# uSD.net
KiCad netlist of a schematic drawn in Altium Designer
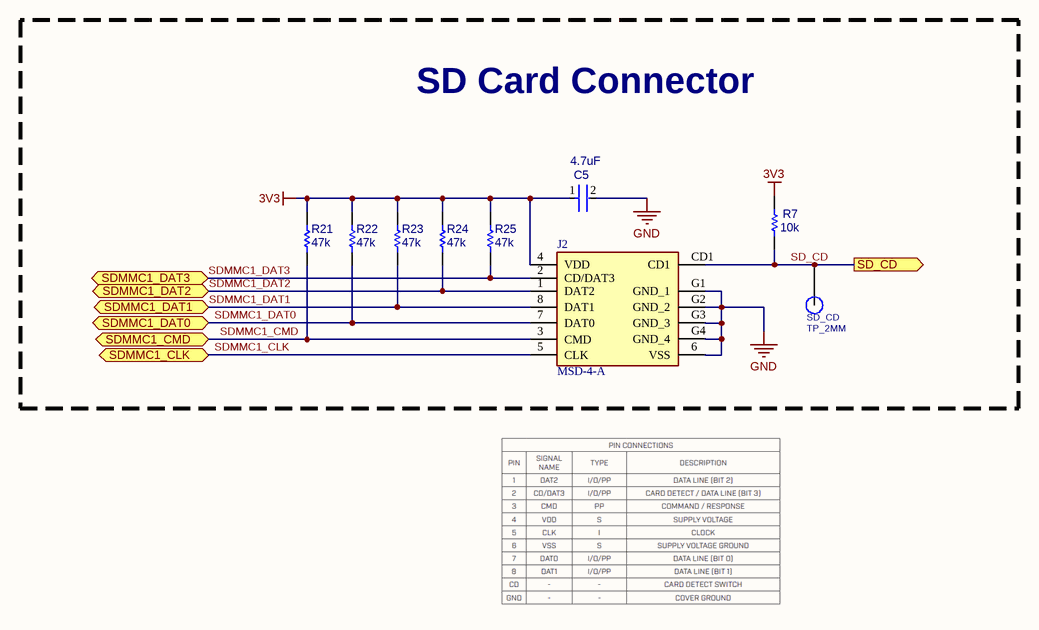
[diagram p0: uSD.SchDoc]

(export (version "E")
  (design (tool "Eeschema 10.0.6"))
  (components
    (comp (ref "C5")
      (value "CC0603KRX7R9BB103")
      (footprint "FP-CC0603-DA-MFG")
      (description "CAP CER 10000PF 50V X7R 0603")
      (fields (field (name "TOLERANCE") "0.1") (field (name "MANUFACTURER") "YAGEO"))
      (libsource (lib "Altium Content Vault") (part "11868f565c42a9108669ba33697ecf6"))
    )
    (comp (ref "J2")
      (value "MSD-4-A")
      (footprint "MSD4A")
      (description "Connector")
      (fields (field (name "MOUSER PART NUMBER") "179-MSD-4-A"))
      (libsource (lib "C2S") (part "MSD-4-A"))
    )
    (comp (ref "R7")
      (value "RC0603JR-070RL")
      (footprint "RESC1608X55X25ML10T15")
      (description "Chip Resistor, 0 Ohm, +/- 5%, 0.1 W, -55 to 155 degC, 0603 (1608 Metric), RoHS, Tape and Reel")
      (fields (field (name "TOLERANCE") "5%") (field (name "MANUFACTURER") "Yageo"))
      (libsource (lib "Altium Content Vault") (part "RES-2"))
    )
    (comp (ref "R21")
      (value "47k")
      (footprint "RESC1608X55X25ML10T15-1")
      (description "Chip Resistor, 10k Ohm, 0.1 W, -55 to 155 degC, 0603 (1608 Metric)")
      (fields
        (field (name "POWER") "100mW")
        (field (name "TOLERANCE") "1%")
        (field (name "CREATED BY") "Micah Randall")
      )
      (libsource (lib "Perth Aerospace Student Team") (part "CMP-009-00006-5"))
    )
    (comp (ref "R22")
      (value "47k")
      (footprint "RESC1608X55X25ML10T15-1")
      (description "Chip Resistor, 10k Ohm, 0.1 W, -55 to 155 degC, 0603 (1608 Metric)")
      (fields
        (field (name "POWER") "100mW")
        (field (name "TOLERANCE") "1%")
        (field (name "CREATED BY") "Micah Randall")
      )
      (libsource (lib "Perth Aerospace Student Team") (part "CMP-009-00006-5"))
    )
    (comp (ref "R23")
      (value "47k")
      (footprint "RESC1608X55X25ML10T15-1")
      (description "Chip Resistor, 10k Ohm, 0.1 W, -55 to 155 degC, 0603 (1608 Metric)")
      (fields
        (field (name "POWER") "100mW")
        (field (name "TOLERANCE") "1%")
        (field (name "CREATED BY") "Micah Randall")
      )
      (libsource (lib "Perth Aerospace Student Team") (part "CMP-009-00006-5"))
    )
    (comp (ref "R24")
      (value "47k")
      (footprint "RESC1608X55X25ML10T15-1")
      (description "Chip Resistor, 10k Ohm, 0.1 W, -55 to 155 degC, 0603 (1608 Metric)")
      (fields
        (field (name "POWER") "100mW")
        (field (name "TOLERANCE") "1%")
        (field (name "CREATED BY") "Micah Randall")
      )
      (libsource (lib "Perth Aerospace Student Team") (part "CMP-009-00006-5"))
    )
    (comp (ref "R25")
      (value "47k")
      (footprint "RESC1608X55X25ML10T15-1")
      (description "Chip Resistor, 10k Ohm, 0.1 W, -55 to 155 degC, 0603 (1608 Metric)")
      (fields
        (field (name "POWER") "100mW")
        (field (name "TOLERANCE") "1%")
        (field (name "CREATED BY") "Micah Randall")
      )
      (libsource (lib "Perth Aerospace Student Team") (part "CMP-009-00006-5"))
    )
    (comp (ref "SD_CD") (value "TP_2MM") (footprint "TESTPOINT 2MM") (libsource (lib "C2S") (part "TP_2MM")))
  )
  (nets
    (net (code "1") (name "/SDMMC1_CLK") (class "Default")
      (node (ref "J2") (pin "5") (pinfunction "CLK_5") (pintype "passive"))
    )
    (net (code "2") (name "/SDMMC1_CMD") (class "Default")
      (node (ref "J2") (pin "3") (pinfunction "CMD_3") (pintype "passive"))
      (node (ref "R21") (pin "1") (pinfunction "1_1") (pintype "passive"))
    )
    (net (code "3") (name "/SDMMC1_DAT0") (class "Default")
      (node (ref "J2") (pin "7") (pinfunction "DAT0_7") (pintype "passive"))
      (node (ref "R22") (pin "1") (pinfunction "1_1") (pintype "passive"))
    )
    (net (code "4") (name "/SDMMC1_DAT1") (class "Default")
      (node (ref "J2") (pin "8") (pinfunction "DAT1_8") (pintype "passive"))
      (node (ref "R23") (pin "1") (pinfunction "1_1") (pintype "passive"))
    )
    (net (code "5") (name "/SDMMC1_DAT2") (class "Default")
      (node (ref "J2") (pin "1") (pinfunction "DAT2_1") (pintype "passive"))
      (node (ref "R24") (pin "1") (pinfunction "1_1") (pintype "passive"))
    )
    (net (code "6") (name "/SDMMC1_DAT3") (class "Default")
      (node (ref "J2") (pin "2") (pinfunction "CD/DAT3_2") (pintype "passive"))
      (node (ref "R25") (pin "1") (pinfunction "1_1") (pintype "passive"))
    )
    (net (code "7") (name "/SD_CD") (class "Default")
      (node (ref "J2") (pin "CD1") (pinfunction "CD1_CD1") (pintype "passive"))
      (node (ref "R7") (pin "2") (pinfunction "2_2") (pintype "passive"))
      (node (ref "SD_CD") (pin "TP") (pinfunction "TP_2MM_TP") (pintype "passive"))
    )
    (net (code "8") (name "3V3") (class "Default")
      (node (ref "C5") (pin "1") (pinfunction "1_1") (pintype "passive"))
      (node (ref "J2") (pin "4") (pinfunction "VDD_4") (pintype "passive"))
      (node (ref "R21") (pin "2") (pinfunction "2_2") (pintype "passive"))
      (node (ref "R22") (pin "2") (pinfunction "2_2") (pintype "passive"))
      (node (ref "R23") (pin "2") (pinfunction "2_2") (pintype "passive"))
      (node (ref "R24") (pin "2") (pinfunction "2_2") (pintype "passive"))
      (node (ref "R25") (pin "2") (pinfunction "2_2") (pintype "passive"))
      (node (ref "R7") (pin "1") (pinfunction "1_1") (pintype "passive"))
    )
    (net (code "9") (name "GND") (class "Default")
      (node (ref "C5") (pin "2") (pinfunction "2_2") (pintype "passive"))
      (node (ref "J2") (pin "6") (pinfunction "VSS_6") (pintype "passive"))
      (node (ref "J2") (pin "G1") (pinfunction "GND_1_G1") (pintype "passive"))
      (node (ref "J2") (pin "G2") (pinfunction "GND_2_G2") (pintype "passive"))
      (node (ref "J2") (pin "G3") (pinfunction "GND_3_G3") (pintype "passive"))
      (node (ref "J2") (pin "G4") (pinfunction "GND_4_G4") (pintype "passive"))
    )
  )
)
